# FMC_HPC_UFL_DEBUG_HPC_CD.net
KiCad netlist of a schematic drawn in Altium Designer
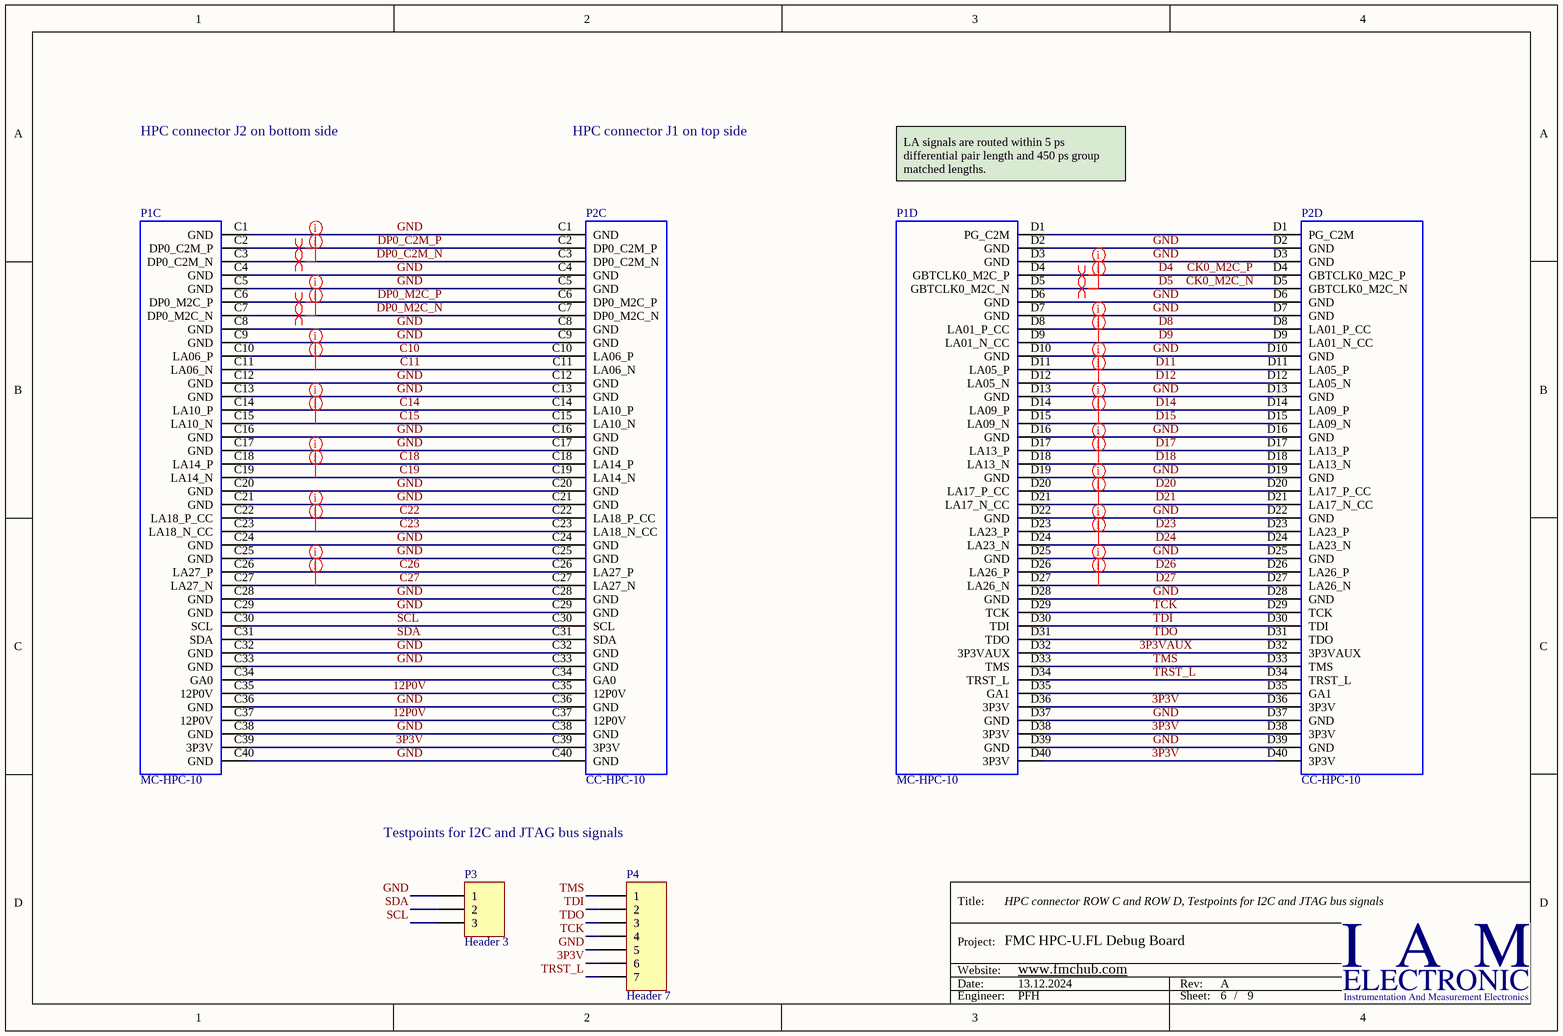
[diagram p0: FMC_HPC_UFL_DEBUG_HPC_CD.SchDoc]

(export (version "E")
  (design (tool "Eeschema 10.0.6"))
  (components
    (comp (ref "P1")
      (value "MC-HPC-10")
      (footprint "ASP-134488-01")
      (description "MC-HPC-10, FMC High-pin count connector, lead free, 400 I/Os, male, 10 mm mated stack height")
      (fields (field (name "MANUFACTURER") "Samtec") (field (name "PART") "ASP-134488-01"))
      (libsource (lib "VITA_57_FMC") (part "MC-HPC-10"))
    )
    (comp (ref "P2")
      (value "CC-HPC-10")
      (footprint "ASP-134486-01")
      (description "CC-HPC-10, FMC High-pin count connector, lead free, 400 I/Os, female, 10 mm mated stack height")
      (fields (field (name "MANUFACTURER") "Samtec") (field (name "PART") "ASP-134486-01"))
      (libsource (lib "VITA_57_FMC") (part "CC-HPC-10"))
    )
    (comp (ref "P3")
      (value "Header 3")
      (footprint "HDR1X3")
      (description "Header, 3-Pin")
      (fields (field (name "PUBLISHER") "Altium Limited"))
      (libsource (lib "Miscellaneous Connectors") (part "Header 3"))
    )
    (comp (ref "P4")
      (value "Header 7")
      (footprint "HDR1X7")
      (description "Header, 7-Pin")
      (fields (field (name "PUBLISHER") "Altium Limited"))
      (libsource (lib "Miscellaneous Connectors") (part "Header 7"))
    )
  )
  (nets
    (net (code "1") (name "/3P3V") (class "Default")
      (node (ref "P1") (pin "C39") (pinfunction "3P3V_C39") (pintype "passive"))
      (node (ref "P1") (pin "D36") (pinfunction "3P3V_D36") (pintype "passive"))
      (node (ref "P1") (pin "D38") (pinfunction "3P3V_D38") (pintype "passive"))
      (node (ref "P1") (pin "D40") (pinfunction "3P3V_D40") (pintype "passive"))
      (node (ref "P2") (pin "C39") (pinfunction "3P3V_C39") (pintype "passive"))
      (node (ref "P2") (pin "D36") (pinfunction "3P3V_D36") (pintype "passive"))
      (node (ref "P2") (pin "D38") (pinfunction "3P3V_D38") (pintype "passive"))
      (node (ref "P2") (pin "D40") (pinfunction "3P3V_D40") (pintype "passive"))
      (node (ref "P4") (pin "6") (pinfunction "6_6") (pintype "passive"))
    )
    (net (code "2") (name "/3P3VAUX") (class "Default")
      (node (ref "P1") (pin "D32") (pinfunction "3P3VAUX_D32") (pintype "passive"))
      (node (ref "P2") (pin "D32") (pinfunction "3P3VAUX_D32") (pintype "passive"))
    )
    (net (code "3") (name "/12P0V") (class "Default")
      (node (ref "P1") (pin "C35") (pinfunction "12P0V_C35") (pintype "passive"))
      (node (ref "P1") (pin "C37") (pinfunction "12P0V_C37") (pintype "passive"))
      (node (ref "P2") (pin "C35") (pinfunction "12P0V_C35") (pintype "passive"))
      (node (ref "P2") (pin "C37") (pinfunction "12P0V_C37") (pintype "passive"))
    )
    (net (code "4") (name "/C10") (class "Default")
      (node (ref "P1") (pin "C10") (pinfunction "LA06_P_C10") (pintype "passive"))
      (node (ref "P2") (pin "C10") (pinfunction "LA06_P_C10") (pintype "passive"))
    )
    (net (code "5") (name "/C11") (class "Default")
      (node (ref "P1") (pin "C11") (pinfunction "LA06_N_C11") (pintype "passive"))
      (node (ref "P2") (pin "C11") (pinfunction "LA06_N_C11") (pintype "passive"))
    )
    (net (code "6") (name "/C14") (class "Default")
      (node (ref "P1") (pin "C14") (pinfunction "LA10_P_C14") (pintype "passive"))
      (node (ref "P2") (pin "C14") (pinfunction "LA10_P_C14") (pintype "passive"))
    )
    (net (code "7") (name "/C15") (class "Default")
      (node (ref "P1") (pin "C15") (pinfunction "LA10_N_C15") (pintype "passive"))
      (node (ref "P2") (pin "C15") (pinfunction "LA10_N_C15") (pintype "passive"))
    )
    (net (code "8") (name "/C18") (class "Default")
      (node (ref "P1") (pin "C18") (pinfunction "LA14_P_C18") (pintype "passive"))
      (node (ref "P2") (pin "C18") (pinfunction "LA14_P_C18") (pintype "passive"))
    )
    (net (code "9") (name "/C19") (class "Default")
      (node (ref "P1") (pin "C19") (pinfunction "LA14_N_C19") (pintype "passive"))
      (node (ref "P2") (pin "C19") (pinfunction "LA14_N_C19") (pintype "passive"))
    )
    (net (code "10") (name "/C22") (class "Default")
      (node (ref "P1") (pin "C22") (pinfunction "LA18_P_CC_C22") (pintype "passive"))
      (node (ref "P2") (pin "C22") (pinfunction "LA18_P_CC_C22") (pintype "passive"))
    )
    (net (code "11") (name "/C23") (class "Default")
      (node (ref "P1") (pin "C23") (pinfunction "LA18_N_CC_C23") (pintype "passive"))
      (node (ref "P2") (pin "C23") (pinfunction "LA18_N_CC_C23") (pintype "passive"))
    )
    (net (code "12") (name "/C26") (class "Default")
      (node (ref "P1") (pin "C26") (pinfunction "LA27_P_C26") (pintype "passive"))
      (node (ref "P2") (pin "C26") (pinfunction "LA27_P_C26") (pintype "passive"))
    )
    (net (code "13") (name "/C27") (class "Default")
      (node (ref "P1") (pin "C27") (pinfunction "LA27_N_C27") (pintype "passive"))
      (node (ref "P2") (pin "C27") (pinfunction "LA27_N_C27") (pintype "passive"))
    )
    (net (code "14") (name "/CK0_M2C_N") (class "Default")
      (node (ref "P1") (pin "D5") (pinfunction "GBTCLK0_M2C_N_D5") (pintype "passive"))
      (node (ref "P2") (pin "D5") (pinfunction "GBTCLK0_M2C_N_D5") (pintype "passive"))
    )
    (net (code "15") (name "/CK0_M2C_P") (class "Default")
      (node (ref "P1") (pin "D4") (pinfunction "GBTCLK0_M2C_P_D4") (pintype "passive"))
      (node (ref "P2") (pin "D4") (pinfunction "GBTCLK0_M2C_P_D4") (pintype "passive"))
    )
    (net (code "16") (name "/D8") (class "Default")
      (node (ref "P1") (pin "D8") (pinfunction "LA01_P_CC_D8") (pintype "passive"))
      (node (ref "P2") (pin "D8") (pinfunction "LA01_P_CC_D8") (pintype "passive"))
    )
    (net (code "17") (name "/D9") (class "Default")
      (node (ref "P1") (pin "D9") (pinfunction "LA01_N_CC_D9") (pintype "passive"))
      (node (ref "P2") (pin "D9") (pinfunction "LA01_N_CC_D9") (pintype "passive"))
    )
    (net (code "18") (name "/D11") (class "Default")
      (node (ref "P1") (pin "D11") (pinfunction "LA05_P_D11") (pintype "passive"))
      (node (ref "P2") (pin "D11") (pinfunction "LA05_P_D11") (pintype "passive"))
    )
    (net (code "19") (name "/D12") (class "Default")
      (node (ref "P1") (pin "D12") (pinfunction "LA05_N_D12") (pintype "passive"))
      (node (ref "P2") (pin "D12") (pinfunction "LA05_N_D12") (pintype "passive"))
    )
    (net (code "20") (name "/D14") (class "Default")
      (node (ref "P1") (pin "D14") (pinfunction "LA09_P_D14") (pintype "passive"))
      (node (ref "P2") (pin "D14") (pinfunction "LA09_P_D14") (pintype "passive"))
    )
    (net (code "21") (name "/D15") (class "Default")
      (node (ref "P1") (pin "D15") (pinfunction "LA09_N_D15") (pintype "passive"))
      (node (ref "P2") (pin "D15") (pinfunction "LA09_N_D15") (pintype "passive"))
    )
    (net (code "22") (name "/D17") (class "Default")
      (node (ref "P1") (pin "D17") (pinfunction "LA13_P_D17") (pintype "passive"))
      (node (ref "P2") (pin "D17") (pinfunction "LA13_P_D17") (pintype "passive"))
    )
    (net (code "23") (name "/D18") (class "Default")
      (node (ref "P1") (pin "D18") (pinfunction "LA13_N_D18") (pintype "passive"))
      (node (ref "P2") (pin "D18") (pinfunction "LA13_N_D18") (pintype "passive"))
    )
    (net (code "24") (name "/D20") (class "Default")
      (node (ref "P1") (pin "D20") (pinfunction "LA17_P_CC_D20") (pintype "passive"))
      (node (ref "P2") (pin "D20") (pinfunction "LA17_P_CC_D20") (pintype "passive"))
    )
    (net (code "25") (name "/D21") (class "Default")
      (node (ref "P1") (pin "D21") (pinfunction "LA17_N_CC_D21") (pintype "passive"))
      (node (ref "P2") (pin "D21") (pinfunction "LA17_N_CC_D21") (pintype "passive"))
    )
    (net (code "26") (name "/D23") (class "Default")
      (node (ref "P1") (pin "D23") (pinfunction "LA23_P_D23") (pintype "passive"))
      (node (ref "P2") (pin "D23") (pinfunction "LA23_P_D23") (pintype "passive"))
    )
    (net (code "27") (name "/D24") (class "Default")
      (node (ref "P1") (pin "D24") (pinfunction "LA23_N_D24") (pintype "passive"))
      (node (ref "P2") (pin "D24") (pinfunction "LA23_N_D24") (pintype "passive"))
    )
    (net (code "28") (name "/D26") (class "Default")
      (node (ref "P1") (pin "D26") (pinfunction "LA26_P_D26") (pintype "passive"))
      (node (ref "P2") (pin "D26") (pinfunction "LA26_P_D26") (pintype "passive"))
    )
    (net (code "29") (name "/D27") (class "Default")
      (node (ref "P1") (pin "D27") (pinfunction "LA26_N_D27") (pintype "passive"))
      (node (ref "P2") (pin "D27") (pinfunction "LA26_N_D27") (pintype "passive"))
    )
    (net (code "30") (name "/DP0_C2M_N") (class "Default")
      (node (ref "P1") (pin "C3") (pinfunction "DP0_C2M_N_C3") (pintype "passive"))
      (node (ref "P2") (pin "C3") (pinfunction "DP0_C2M_N_C3") (pintype "passive"))
    )
    (net (code "31") (name "/DP0_C2M_P") (class "Default")
      (node (ref "P1") (pin "C2") (pinfunction "DP0_C2M_P_C2") (pintype "passive"))
      (node (ref "P2") (pin "C2") (pinfunction "DP0_C2M_P_C2") (pintype "passive"))
    )
    (net (code "32") (name "/DP0_M2C_N") (class "Default")
      (node (ref "P1") (pin "C7") (pinfunction "DP0_M2C_N_C7") (pintype "passive"))
      (node (ref "P2") (pin "C7") (pinfunction "DP0_M2C_N_C7") (pintype "passive"))
    )
    (net (code "33") (name "/DP0_M2C_P") (class "Default")
      (node (ref "P1") (pin "C6") (pinfunction "DP0_M2C_P_C6") (pintype "passive"))
      (node (ref "P2") (pin "C6") (pinfunction "DP0_M2C_P_C6") (pintype "passive"))
    )
    (net (code "34") (name "/GND") (class "Default")
      (node (ref "P1") (pin "C1") (pinfunction "GND_C1") (pintype "passive"))
      (node (ref "P1") (pin "C12") (pinfunction "GND_C12") (pintype "passive"))
      (node (ref "P1") (pin "C13") (pinfunction "GND_C13") (pintype "passive"))
      (node (ref "P1") (pin "C16") (pinfunction "GND_C16") (pintype "passive"))
      (node (ref "P1") (pin "C17") (pinfunction "GND_C17") (pintype "passive"))
      (node (ref "P1") (pin "C20") (pinfunction "GND_C20") (pintype "passive"))
      (node (ref "P1") (pin "C21") (pinfunction "GND_C21") (pintype "passive"))
      (node (ref "P1") (pin "C24") (pinfunction "GND_C24") (pintype "passive"))
      (node (ref "P1") (pin "C25") (pinfunction "GND_C25") (pintype "passive"))
      (node (ref "P1") (pin "C28") (pinfunction "GND_C28") (pintype "passive"))
      (node (ref "P1") (pin "C29") (pinfunction "GND_C29") (pintype "passive"))
      (node (ref "P1") (pin "C32") (pinfunction "GND_C32") (pintype "passive"))
      (node (ref "P1") (pin "C33") (pinfunction "GND_C33") (pintype "passive"))
      (node (ref "P1") (pin "C36") (pinfunction "GND_C36") (pintype "passive"))
      (node (ref "P1") (pin "C38") (pinfunction "GND_C38") (pintype "passive"))
      (node (ref "P1") (pin "C4") (pinfunction "GND_C4") (pintype "passive"))
      (node (ref "P1") (pin "C40") (pinfunction "GND_C40") (pintype "passive"))
      (node (ref "P1") (pin "C5") (pinfunction "GND_C5") (pintype "passive"))
      (node (ref "P1") (pin "C8") (pinfunction "GND_C8") (pintype "passive"))
      (node (ref "P1") (pin "C9") (pinfunction "GND_C9") (pintype "passive"))
      (node (ref "P1") (pin "D10") (pinfunction "GND_D10") (pintype "passive"))
      (node (ref "P1") (pin "D13") (pinfunction "GND_D13") (pintype "passive"))
      (node (ref "P1") (pin "D16") (pinfunction "GND_D16") (pintype "passive"))
      (node (ref "P1") (pin "D19") (pinfunction "GND_D19") (pintype "passive"))
      (node (ref "P1") (pin "D2") (pinfunction "GND_D2") (pintype "passive"))
      (node (ref "P1") (pin "D22") (pinfunction "GND_D22") (pintype "passive"))
      (node (ref "P1") (pin "D25") (pinfunction "GND_D25") (pintype "passive"))
      (node (ref "P1") (pin "D28") (pinfunction "GND_D28") (pintype "passive"))
      (node (ref "P1") (pin "D3") (pinfunction "GND_D3") (pintype "passive"))
      (node (ref "P1") (pin "D37") (pinfunction "GND_D37") (pintype "passive"))
      (node (ref "P1") (pin "D39") (pinfunction "GND_D39") (pintype "passive"))
      (node (ref "P1") (pin "D6") (pinfunction "GND_D6") (pintype "passive"))
      (node (ref "P1") (pin "D7") (pinfunction "GND_D7") (pintype "passive"))
      (node (ref "P2") (pin "C1") (pinfunction "GND_C1") (pintype "passive"))
      (node (ref "P2") (pin "C12") (pinfunction "GND_C12") (pintype "passive"))
      (node (ref "P2") (pin "C13") (pinfunction "GND_C13") (pintype "passive"))
      (node (ref "P2") (pin "C16") (pinfunction "GND_C16") (pintype "passive"))
      (node (ref "P2") (pin "C17") (pinfunction "GND_C17") (pintype "passive"))
      (node (ref "P2") (pin "C20") (pinfunction "GND_C20") (pintype "passive"))
      (node (ref "P2") (pin "C21") (pinfunction "GND_C21") (pintype "passive"))
      (node (ref "P2") (pin "C24") (pinfunction "GND_C24") (pintype "passive"))
      (node (ref "P2") (pin "C25") (pinfunction "GND_C25") (pintype "passive"))
      (node (ref "P2") (pin "C28") (pinfunction "GND_C28") (pintype "passive"))
      (node (ref "P2") (pin "C29") (pinfunction "GND_C29") (pintype "passive"))
      (node (ref "P2") (pin "C32") (pinfunction "GND_C32") (pintype "passive"))
      (node (ref "P2") (pin "C33") (pinfunction "GND_C33") (pintype "passive"))
      (node (ref "P2") (pin "C36") (pinfunction "GND_C36") (pintype "passive"))
      (node (ref "P2") (pin "C38") (pinfunction "GND_C38") (pintype "passive"))
      (node (ref "P2") (pin "C4") (pinfunction "GND_C4") (pintype "passive"))
      (node (ref "P2") (pin "C40") (pinfunction "GND_C40") (pintype "passive"))
      (node (ref "P2") (pin "C5") (pinfunction "GND_C5") (pintype "passive"))
      (node (ref "P2") (pin "C8") (pinfunction "GND_C8") (pintype "passive"))
      (node (ref "P2") (pin "C9") (pinfunction "GND_C9") (pintype "passive"))
      (node (ref "P2") (pin "D10") (pinfunction "GND_D10") (pintype "passive"))
      (node (ref "P2") (pin "D13") (pinfunction "GND_D13") (pintype "passive"))
      (node (ref "P2") (pin "D16") (pinfunction "GND_D16") (pintype "passive"))
      (node (ref "P2") (pin "D19") (pinfunction "GND_D19") (pintype "passive"))
      (node (ref "P2") (pin "D2") (pinfunction "GND_D2") (pintype "passive"))
      (node (ref "P2") (pin "D22") (pinfunction "GND_D22") (pintype "passive"))
      (node (ref "P2") (pin "D25") (pinfunction "GND_D25") (pintype "passive"))
      (node (ref "P2") (pin "D28") (pinfunction "GND_D28") (pintype "passive"))
      (node (ref "P2") (pin "D3") (pinfunction "GND_D3") (pintype "passive"))
      (node (ref "P2") (pin "D37") (pinfunction "GND_D37") (pintype "passive"))
      (node (ref "P2") (pin "D39") (pinfunction "GND_D39") (pintype "passive"))
      (node (ref "P2") (pin "D6") (pinfunction "GND_D6") (pintype "passive"))
      (node (ref "P2") (pin "D7") (pinfunction "GND_D7") (pintype "passive"))
      (node (ref "P3") (pin "1") (pinfunction "1_1") (pintype "passive"))
      (node (ref "P4") (pin "5") (pinfunction "5_5") (pintype "passive"))
    )
    (net (code "35") (name "/SCL") (class "Default")
      (node (ref "P1") (pin "C30") (pinfunction "SCL_C30") (pintype "passive"))
      (node (ref "P2") (pin "C30") (pinfunction "SCL_C30") (pintype "passive"))
      (node (ref "P3") (pin "3") (pinfunction "3_3") (pintype "passive"))
    )
    (net (code "36") (name "/SDA") (class "Default")
      (node (ref "P1") (pin "C31") (pinfunction "SDA_C31") (pintype "passive"))
      (node (ref "P2") (pin "C31") (pinfunction "SDA_C31") (pintype "passive"))
      (node (ref "P3") (pin "2") (pinfunction "2_2") (pintype "passive"))
    )
    (net (code "37") (name "/TCK") (class "Default")
      (node (ref "P1") (pin "D29") (pinfunction "TCK_D29") (pintype "passive"))
      (node (ref "P2") (pin "D29") (pinfunction "TCK_D29") (pintype "passive"))
      (node (ref "P4") (pin "4") (pinfunction "4_4") (pintype "passive"))
    )
    (net (code "38") (name "/TDI") (class "Default")
      (node (ref "P1") (pin "D30") (pinfunction "TDI_D30") (pintype "passive"))
      (node (ref "P2") (pin "D30") (pinfunction "TDI_D30") (pintype "passive"))
      (node (ref "P4") (pin "2") (pinfunction "2_2") (pintype "passive"))
    )
    (net (code "39") (name "/TDO") (class "Default")
      (node (ref "P1") (pin "D31") (pinfunction "TDO_D31") (pintype "passive"))
      (node (ref "P2") (pin "D31") (pinfunction "TDO_D31") (pintype "passive"))
      (node (ref "P4") (pin "3") (pinfunction "3_3") (pintype "passive"))
    )
    (net (code "40") (name "/TMS") (class "Default")
      (node (ref "P1") (pin "D33") (pinfunction "TMS_D33") (pintype "passive"))
      (node (ref "P2") (pin "D33") (pinfunction "TMS_D33") (pintype "passive"))
      (node (ref "P4") (pin "1") (pinfunction "1_1") (pintype "passive"))
    )
    (net (code "41") (name "/TRST_L") (class "Default")
      (node (ref "P1") (pin "D34") (pinfunction "TRST_L_D34") (pintype "passive"))
      (node (ref "P2") (pin "D34") (pinfunction "TRST_L_D34") (pintype "passive"))
      (node (ref "P4") (pin "7") (pinfunction "7_7") (pintype "passive"))
    )
    (net (code "42") (name "Net-(P1C-GA0)") (class "Default")
      (node (ref "P1") (pin "C34") (pinfunction "GA0_C34") (pintype "passive"))
      (node (ref "P2") (pin "C34") (pinfunction "GA0_C34") (pintype "passive"))
    )
    (net (code "43") (name "Net-(P1D-GA1)") (class "Default")
      (node (ref "P1") (pin "D35") (pinfunction "GA1_D35") (pintype "passive"))
      (node (ref "P2") (pin "D35") (pinfunction "GA1_D35") (pintype "passive"))
    )
    (net (code "44") (name "Net-(P1D-PG_C2M)") (class "Default")
      (node (ref "P1") (pin "D1") (pinfunction "PG_C2M_D1") (pintype "passive"))
      (node (ref "P2") (pin "D1") (pinfunction "PG_C2M_D1") (pintype "passive"))
    )
  )
)
